# Shema.net
KiCad netlist of a schematic drawn in Altium Designer
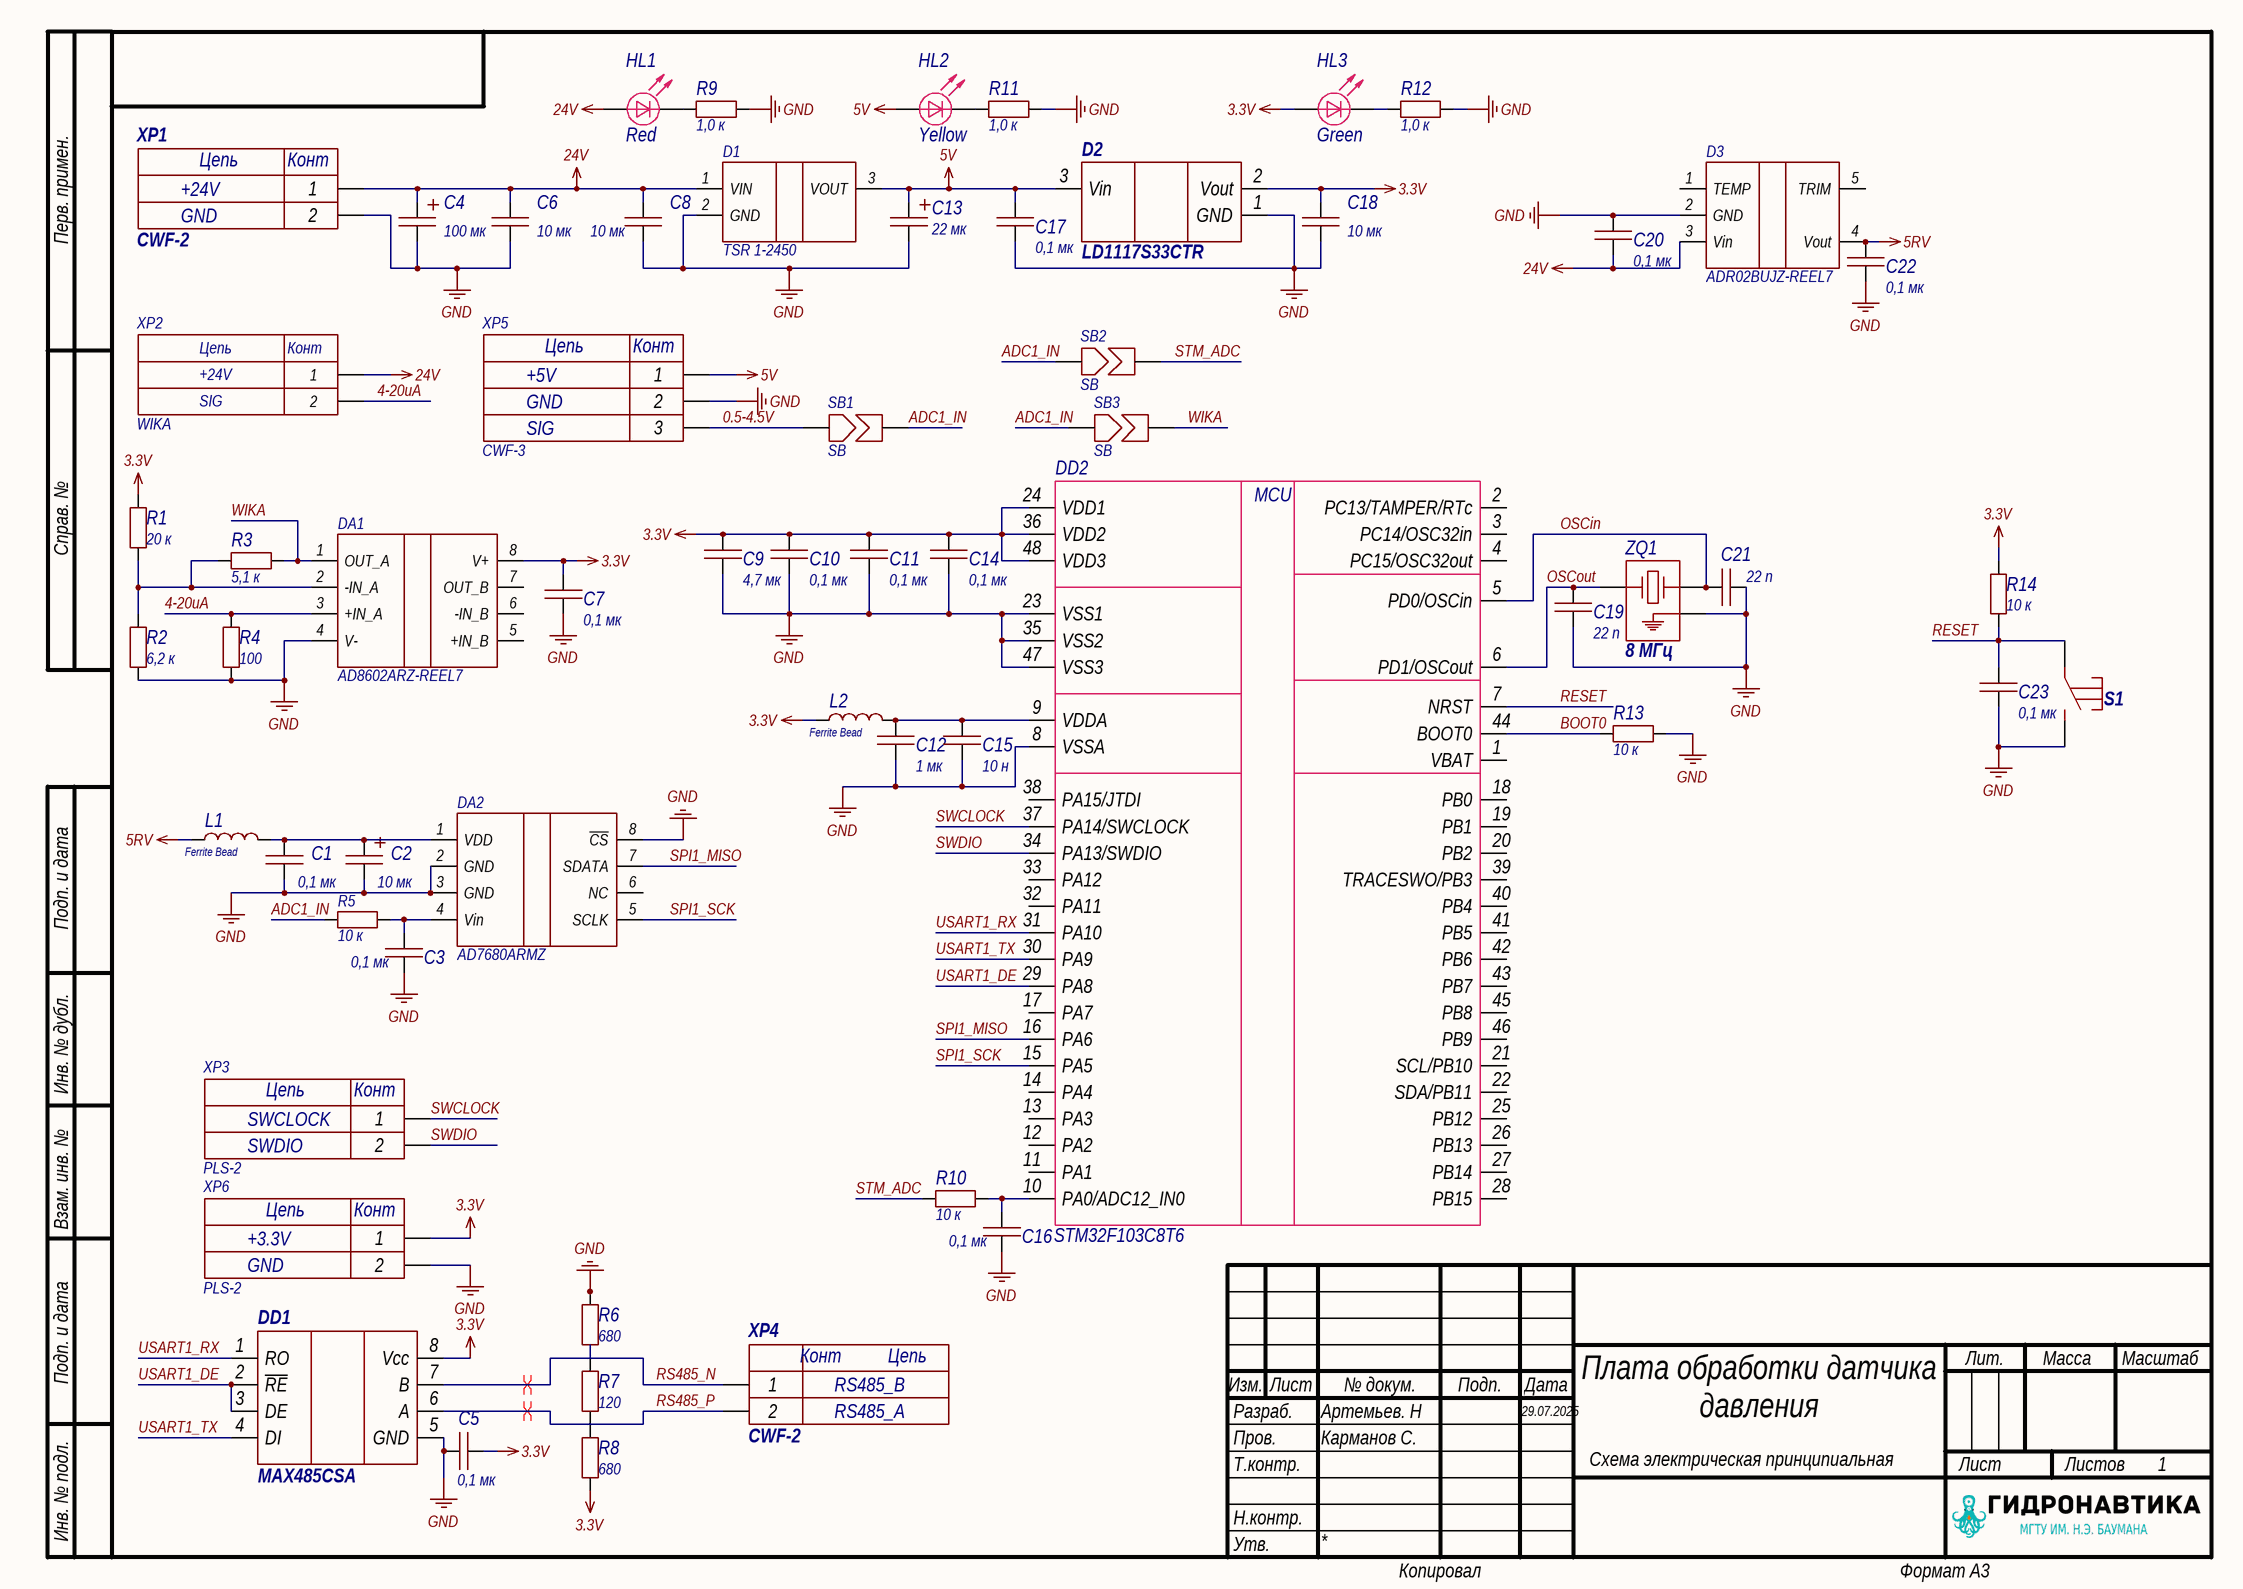
[diagram p0: Shema.SchDoc]

(export (version "E")
  (design (tool "Eeschema 10.0.6"))
  (components
    (comp (ref "C1")
      (value "0,1 мк")
      (footprint "0603C")
      (description "Конденсатор")
      (fields (field (name "PART NUMBER") "Capacitor_0,1u_10_50V_X7R_0603C") (field (name "TOLERANCE") "0,1"))
      (libsource (lib "Hydrolib") (part "Capacitor"))
    )
    (comp (ref "C2")
      (value "10 мк")
      (footprint "TC_A")
      (description "Танталовый конденсатор")
      (fields (field (name "PART NUMBER") "Capacitor_10u_10_50V_TC_A") (field (name "TOLERANCE") "0,1"))
      (libsource (lib "Hydrolib") (part "Capacitor_polar"))
    )
    (comp (ref "C3")
      (value "0,1 мк")
      (footprint "0603C")
      (description "Конденсатор")
      (fields (field (name "PART NUMBER") "Capacitor_0,1u_10_50V_X7R_0603C") (field (name "TOLERANCE") "0,1"))
      (libsource (lib "Hydrolib") (part "Capacitor"))
    )
    (comp (ref "C4")
      (value "100 мк")
      (footprint "TC_A")
      (description "Танталовый конденсатор")
      (fields (field (name "PART NUMBER") "Capacitor_100u_10_50V_TC_A") (field (name "TOLERANCE") "0,1"))
      (libsource (lib "Hydrolib") (part "Capacitor_polar"))
    )
    (comp (ref "C5")
      (value "0,1 мк")
      (footprint "0603C")
      (description "Конденсатор")
      (fields (field (name "PART NUMBER") "Capacitor_0,1u_10_50V_X7R_0603C") (field (name "TOLERANCE") "0,1"))
      (libsource (lib "Hydrolib") (part "Capacitor"))
    )
    (comp (ref "C6")
      (value "10 мк")
      (footprint "1210C")
      (description "Конденсатор")
      (fields (field (name "PART NUMBER") "Capacitor_10u_10_35V_X7R_1210C") (field (name "TOLERANCE") "0,1"))
      (libsource (lib "Hydrolib") (part "Capacitor"))
    )
    (comp (ref "C7")
      (value "0,1 мк")
      (footprint "0603C")
      (description "Конденсатор")
      (fields (field (name "PART NUMBER") "Capacitor_0,1u_10_50V_X7R_0603C") (field (name "TOLERANCE") "0,1"))
      (libsource (lib "Hydrolib") (part "Capacitor"))
    )
    (comp (ref "C8")
      (value "10 мк")
      (footprint "1210C")
      (description "Конденсатор")
      (fields (field (name "PART NUMBER") "Capacitor_10u_10_35V_X7R_1210C") (field (name "TOLERANCE") "0,1"))
      (libsource (lib "Hydrolib") (part "Capacitor"))
    )
    (comp (ref "C9")
      (value "4,7 мк")
      (footprint "1206C")
      (description "Конденсатор")
      (fields (field (name "PART NUMBER") "Capacitor_4,7u_10_50V_X7R_1206C") (field (name "TOLERANCE") "0,1"))
      (libsource (lib "Hydrolib") (part "Capacitor"))
    )
    (comp (ref "C10")
      (value "0,1 мк")
      (footprint "0603C")
      (description "Конденсатор")
      (fields (field (name "PART NUMBER") "Capacitor_0,1u_10_50V_X7R_0603C") (field (name "TOLERANCE") "0,1"))
      (libsource (lib "Hydrolib") (part "Capacitor"))
    )
    (comp (ref "C11")
      (value "0,1 мк")
      (footprint "0603C")
      (description "Конденсатор")
      (fields (field (name "PART NUMBER") "Capacitor_0,1u_10_50V_X7R_0603C") (field (name "TOLERANCE") "0,1"))
      (libsource (lib "Hydrolib") (part "Capacitor"))
    )
    (comp (ref "C12")
      (value "1 мк")
      (footprint "0603C")
      (description "Конденсатор")
      (fields (field (name "PART NUMBER") "Capacitor_1u_10_50V_X7R_0603C") (field (name "TOLERANCE") "0,1"))
      (libsource (lib "Hydrolib") (part "Capacitor"))
    )
    (comp (ref "C13")
      (value "22 мк")
      (footprint "TC_A")
      (description "Танталовый конденсатор")
      (fields (field (name "PART NUMBER") "Capacitor_22u_10_50V_TC_A") (field (name "TOLERANCE") "0,1"))
      (libsource (lib "Hydrolib") (part "Capacitor_polar"))
    )
    (comp (ref "C14")
      (value "0,1 мк")
      (footprint "0603C")
      (description "Конденсатор")
      (fields (field (name "PART NUMBER") "Capacitor_0,1u_10_50V_X7R_0603C") (field (name "TOLERANCE") "0,1"))
      (libsource (lib "Hydrolib") (part "Capacitor"))
    )
    (comp (ref "C15")
      (value "10 н")
      (footprint "0603C")
      (description "Конденсатор")
      (fields (field (name "PART NUMBER") "Capacitor_10n_10_50V_X7R_0603C") (field (name "TOLERANCE") "0,1"))
      (libsource (lib "Hydrolib") (part "Capacitor"))
    )
    (comp (ref "C16")
      (value "0,1 мк")
      (footprint "0603C")
      (description "Конденсатор")
      (fields (field (name "PART NUMBER") "Capacitor_0,1u_10_50V_X7R_0603C") (field (name "TOLERANCE") "0,1"))
      (libsource (lib "Hydrolib") (part "Capacitor"))
    )
    (comp (ref "C17")
      (value "0,1 мк")
      (footprint "0603C")
      (description "Конденсатор")
      (fields (field (name "PART NUMBER") "Capacitor_0,1u_10_50V_X7R_0603C") (field (name "TOLERANCE") "0,1"))
      (libsource (lib "Hydrolib") (part "Capacitor"))
    )
    (comp (ref "C18")
      (value "10 мк")
      (footprint "1210C")
      (description "Конденсатор")
      (fields (field (name "PART NUMBER") "Capacitor_10u_10_35V_X7R_1210C") (field (name "TOLERANCE") "0,1"))
      (libsource (lib "Hydrolib") (part "Capacitor"))
    )
    (comp (ref "C19")
      (value "22 п")
      (footprint "0603C")
      (description "Конденсатор")
      (fields (field (name "PART NUMBER") "Capacitor_22p_5_50V_X7R_0603C") (field (name "TOLERANCE") "0,05"))
      (libsource (lib "Hydrolib") (part "Capacitor"))
    )
    (comp (ref "C20")
      (value "0,1 мк")
      (footprint "0603C")
      (description "Конденсатор")
      (fields (field (name "PART NUMBER") "Capacitor_0,1u_10_50V_X7R_0603C") (field (name "TOLERANCE") "0,1"))
      (libsource (lib "Hydrolib") (part "Capacitor"))
    )
    (comp (ref "C21")
      (value "22 п")
      (footprint "0603C")
      (description "Конденсатор")
      (fields (field (name "PART NUMBER") "Capacitor_22p_5_50V_X7R_0603C") (field (name "TOLERANCE") "0,05"))
      (libsource (lib "Hydrolib") (part "Capacitor"))
    )
    (comp (ref "C22")
      (value "0,1 мк")
      (footprint "0603C")
      (description "Конденсатор")
      (fields (field (name "PART NUMBER") "Capacitor_0,1u_10_50V_X7R_0603C") (field (name "TOLERANCE") "0,1"))
      (libsource (lib "Hydrolib") (part "Capacitor"))
    )
    (comp (ref "C23")
      (value "0,1 мк")
      (footprint "0603C")
      (description "Конденсатор")
      (fields (field (name "PART NUMBER") "Capacitor_0,1u_10_50V_X7R_0603C") (field (name "TOLERANCE") "0,1"))
      (libsource (lib "Hydrolib") (part "Capacitor"))
    )
    (comp (ref "D1")
      (value "TSR 1-2450")
      (footprint "SIP3")
      (description "DC/DC преобразователь, 5Вт, вход 6.5-36В, выход 5В/ 1А")
      (libsource (lib "Hydrolib") (part "TSR 1-2450"))
    )
    (comp (ref "D2")
      (value "LD1117S33CTR")
      (footprint "SOT223")
      (description "Линейный стабилизатор напряжения")
      (libsource (lib "Hydrolib") (part "LD1117S33CTR"))
    )
    (comp (ref "D3")
      (value "ADR02BUJZ-REEL7")
      (footprint "SOT23-5")
      (description "Источник опорного напряжения, 5 В")
      (libsource (lib "Hydrolib") (part "ADR02BUJZ-REEL7"))
    )
    (comp (ref "DA1")
      (value "AD8602ARZ-REEL7")
      (footprint "SOIC-8")
      (description "2-х канальный прецизионный, широкополосный операционный усилитель с однополярным питанием")
      (libsource (lib "Hydrolib") (part "AD8602"))
    )
    (comp (ref "DA2")
      (value "AD7680ARMZ")
      (footprint "MSOP-8")
      (description "16-бит АЦП, SAR, 100Квыборок/с")
      (libsource (lib "Hydrolib") (part "AD7680ARMZ"))
    )
    (comp (ref "DD1")
      (value "MAX485CSA")
      (footprint "SOIC-8")
      (description "RS-485 приёмопередатчик")
      (libsource (lib "Hydrolib") (part "MAX485CSA"))
    )
    (comp (ref "DD2")
      (value "STM32F103C8T6")
      (footprint "LQFP48")
      (description "Микроконтроллер")
      (fields (field (name "MANUFACTURER") "ST Microelectronics") (field (name "VALUE1") "MCU"))
      (libsource (lib "Hydrolib") (part "STM32F103C8T6"))
    )
    (comp (ref "HL1")
      (value "LED")
      (footprint "0805D")
      (description "Светодиод")
      (fields (field (name "COLOR") "Red"))
      (libsource (lib "Hydrolib") (part "LED"))
    )
    (comp (ref "HL2")
      (value "LED")
      (footprint "0805D")
      (description "Светодиод")
      (fields (field (name "COLOR") "Yellow"))
      (libsource (lib "Hydrolib") (part "LED"))
    )
    (comp (ref "HL3")
      (value "LED")
      (footprint "0805D")
      (description "Светодиод")
      (fields (field (name "COLOR") "Green"))
      (libsource (lib "Hydrolib") (part "LED"))
    )
    (comp (ref "L1")
      (value "Ferrite Bead")
      (footprint "0603L")
      (fields (field (name "PART NUMBER") "Inductance"))
      (libsource (lib "Hydrolib") (part "Inductance"))
    )
    (comp (ref "L2")
      (value "Ferrite Bead")
      (footprint "0603L")
      (fields (field (name "PART NUMBER") "Inductance"))
      (libsource (lib "Hydrolib") (part "Inductance"))
    )
    (comp (ref "R1")
      (value "20 к")
      (footprint "0603R")
      (description "Резистор номиналом 20 кОм и точностью 1%")
      (fields (field (name "PART NUMBER") "Resistor_20k_1_0603") (field (name "TOLERANCE") "1%"))
      (libsource (lib "") (part "Resistor_1"))
    )
    (comp (ref "R2")
      (value "6,2 к")
      (footprint "0603R")
      (description "Резистор номиналом 6,2 кОм и точностью 1%")
      (fields (field (name "PART NUMBER") "Resistor_6.2k_1_0603") (field (name "TOLERANCE") "1%"))
      (libsource (lib "") (part "Resistor_1"))
    )
    (comp (ref "R3")
      (value "5,1 к")
      (footprint "0603R")
      (description "Резистор номиналом 5,1 кОм и точностью 1%")
      (fields (field (name "PART NUMBER") "Resistor_5.1k_1_0603") (field (name "TOLERANCE") "1%"))
      (libsource (lib "Hydrolib") (part "Resistor"))
    )
    (comp (ref "R4")
      (value "100")
      (footprint "0603R")
      (description "Резистор номиналом 100 Ом и точностью 1%")
      (fields (field (name "PART NUMBER") "Resistor_100_1_0603") (field (name "TOLERANCE") "1%"))
      (libsource (lib "") (part "Resistor_2"))
    )
    (comp (ref "R5")
      (value "10 к")
      (footprint "0603R")
      (description "Резистор номиналом 10 кОм и точностью 1%")
      (fields (field (name "PART NUMBER") "Resistor_10k_1_0603") (field (name "TOLERANCE") "1%"))
      (libsource (lib "Hydrolib") (part "Resistor"))
    )
    (comp (ref "R6")
      (value "680")
      (footprint "0603R")
      (description "Резистор номиналом 680 Ом и точностью 1%")
      (fields (field (name "PART NUMBER") "Resistor_680_1_0603") (field (name "TOLERANCE") "1%"))
      (libsource (lib "") (part "Resistor_1"))
    )
    (comp (ref "R7")
      (value "120")
      (footprint "1206R")
      (description "Резистор номиналом 120 Ом и точностью 1%")
      (fields (field (name "PART NUMBER") "Resistor_120_1_0603") (field (name "TOLERANCE") "1%"))
      (libsource (lib "") (part "Resistor_1"))
    )
    (comp (ref "R8")
      (value "680")
      (footprint "0603R")
      (description "Резистор номиналом 680 Ом и точностью 1%")
      (fields (field (name "PART NUMBER") "Resistor_680_1_0603") (field (name "TOLERANCE") "1%"))
      (libsource (lib "") (part "Resistor_1"))
    )
    (comp (ref "R9")
      (value "1,0 к")
      (footprint "0603R")
      (description "Резистор номиналом 1,0 кОм и точностью 1%")
      (fields (field (name "PART NUMBER") "Resistor_1.0k_1_0603") (field (name "TOLERANCE") "1%"))
      (libsource (lib "Hydrolib") (part "Resistor"))
    )
    (comp (ref "R10")
      (value "10 к")
      (footprint "0603R")
      (description "Резистор номиналом 10 кОм и точностью 1%")
      (fields (field (name "PART NUMBER") "Resistor_10k_1_0603") (field (name "TOLERANCE") "1%"))
      (libsource (lib "Hydrolib") (part "Resistor"))
    )
    (comp (ref "R11")
      (value "1,0 к")
      (footprint "0603R")
      (description "Резистор номиналом 1,0 кОм и точностью 1%")
      (fields (field (name "PART NUMBER") "Resistor_1.0k_1_0603") (field (name "TOLERANCE") "1%"))
      (libsource (lib "Hydrolib") (part "Resistor"))
    )
    (comp (ref "R12")
      (value "1,0 к")
      (footprint "0603R")
      (description "Резистор номиналом 1,0 кОм и точностью 1%")
      (fields (field (name "PART NUMBER") "Resistor_1.0k_1_0603") (field (name "TOLERANCE") "1%"))
      (libsource (lib "Hydrolib") (part "Resistor"))
    )
    (comp (ref "R13")
      (value "10 к")
      (footprint "0603R")
      (description "Резистор номиналом 10 кОм и точностью 1%")
      (fields (field (name "PART NUMBER") "Resistor_10k_1_0603") (field (name "TOLERANCE") "1%"))
      (libsource (lib "Hydrolib") (part "Resistor"))
    )
    (comp (ref "R14")
      (value "10 к")
      (footprint "0603R")
      (description "Резистор номиналом 10 кОм и точностью 1%")
      (fields (field (name "PART NUMBER") "Resistor_10k_1_0603") (field (name "TOLERANCE") "1%"))
      (libsource (lib "") (part "Resistor_2"))
    )
    (comp (ref "S1")
      (value "Tact_button")
      (footprint "Button_SMD_10mm")
      (description "Тактовая кнопка")
      (libsource (lib "Hydrolib") (part "Tact_button"))
    )
    (comp (ref "SB1")
      (value "SB")
      (footprint "0805SB")
      (description "Solder bridge, мост припоя, запаиваемая перемычка, net tie, jumper")
      (libsource (lib "Hydrolib") (part "SB"))
    )
    (comp (ref "SB2")
      (value "SB")
      (footprint "0805SB")
      (description "Solder bridge, мост припоя, запаиваемая перемычка, net tie, jumper")
      (libsource (lib "Hydrolib") (part "SB"))
    )
    (comp (ref "SB3")
      (value "SB")
      (footprint "0805SB")
      (description "Solder bridge, мост припоя, запаиваемая перемычка, net tie, jumper")
      (libsource (lib "Hydrolib") (part "SB"))
    )
    (comp (ref "XP1")
      (value "CWF-2")
      (footprint "CWF-2")
      (description "2-пиновый разъем с ключом")
      (fields (field (name "VALUE2") "GND") (field (name "VALUE1") "+24V"))
      (libsource (lib "Hydrolib") (part "Conn_2pin"))
    )
    (comp (ref "XP2") (value "WIKA") (footprint "WIKA_PCB") (libsource (lib "Hydrolib") (part "WIKA")))
    (comp (ref "XP3")
      (value "PLS-2")
      (footprint "PLS2")
      (description "Гребенка 2 пина")
      (fields (field (name "VALUE2") "SWDIO") (field (name "VALUE1") "SWCLOCK"))
      (libsource (lib "Hydrolib") (part "Conn_2pin"))
    )
    (comp (ref "XP4")
      (value "CWF-2")
      (footprint "CWF-2")
      (description "2-пиновый разъем с ключом")
      (fields (field (name "VALUE2") "RS485_A") (field (name "VALUE1") "RS485_B"))
      (libsource (lib "Hydrolib") (part "Conn_2pin"))
    )
    (comp (ref "XP5")
      (value "CWF-3")
      (footprint "CWF-3")
      (description "3-пиновый разъем с ключом")
      (fields (field (name "VALUE3") "SIG") (field (name "VALUE2") "GND") (field (name "VALUE1") "+5V"))
      (libsource (lib "Hydrolib") (part "Conn_3pin"))
    )
    (comp (ref "XP6")
      (value "PLS-2")
      (footprint "PLS2")
      (description "Гребенка 2 пина")
      (fields (field (name "VALUE2") "GND") (field (name "VALUE1") "+3.3V"))
      (libsource (lib "Hydrolib") (part "Conn_2pin"))
    )
    (comp (ref "ZQ1")
      (value "8 МГц")
      (footprint "QSMD3.2x2.5")
      (description "Кварцевый резонатор с входом земли")
      (fields (field (name "PART NUMBER") "XTAL_GND"))
      (libsource (lib "Hydrolib") (part "XTAL_GND"))
    )
  )
  (nets
    (net (code "1") (name "/0.5-4.5V") (class "Default")
      (node (ref "SB1") (pin "1") (pinfunction "1_1") (pintype "passive"))
      (node (ref "XP5") (pin "3") (pinfunction "3_3") (pintype "passive"))
    )
    (net (code "2") (name "/4-20uA") (class "Default")
      (node (ref "DA1") (pin "3") (pinfunction "+IN_A_3") (pintype "passive"))
      (node (ref "R4") (pin "1") (pinfunction "1_1") (pintype "passive"))
      (node (ref "XP2") (pin "2") (pinfunction "2_2") (pintype "passive"))
    )
    (net (code "3") (name "/ADC1_IN") (class "Default")
      (node (ref "R5") (pin "1") (pinfunction "1_1") (pintype "passive"))
      (node (ref "SB1") (pin "2") (pinfunction "2_2") (pintype "passive"))
      (node (ref "SB2") (pin "1") (pinfunction "1_1") (pintype "passive"))
      (node (ref "SB3") (pin "1") (pinfunction "1_1") (pintype "passive"))
    )
    (net (code "4") (name "/BOOT0") (class "Default")
      (node (ref "DD2") (pin "44") (pinfunction "BOOT0_44") (pintype "passive"))
      (node (ref "R13") (pin "1") (pinfunction "1_1") (pintype "passive"))
    )
    (net (code "5") (name "/OSCin") (class "Default")
      (node (ref "C21") (pin "2") (pinfunction "2_2") (pintype "passive"))
      (node (ref "DD2") (pin "5") (pinfunction "PD0/OSCin_5") (pintype "passive"))
      (node (ref "ZQ1") (pin "2") (pinfunction "2_2") (pintype "passive"))
    )
    (net (code "6") (name "/OSCout") (class "Default")
      (node (ref "C19") (pin "1") (pinfunction "1_1") (pintype "passive"))
      (node (ref "DD2") (pin "6") (pinfunction "PD1/OSCout_6") (pintype "passive"))
      (node (ref "ZQ1") (pin "1") (pinfunction "1_1") (pintype "passive"))
    )
    (net (code "7") (name "/RESET") (class "Default")
      (node (ref "C23") (pin "1") (pinfunction "1_1") (pintype "passive"))
      (node (ref "DD2") (pin "7") (pinfunction "NRST_7") (pintype "passive"))
      (node (ref "R14") (pin "2") (pinfunction "2_2") (pintype "passive"))
      (node (ref "S1") (pin "1") (pinfunction "1_1") (pintype "passive"))
    )
    (net (code "8") (name "/RS485_N") (class "Default")
      (node (ref "DD1") (pin "7") (pinfunction "B_7") (pintype "passive"))
      (node (ref "R6") (pin "1") (pinfunction "1_1") (pintype "passive"))
      (node (ref "R7") (pin "2") (pinfunction "2_2") (pintype "passive"))
      (node (ref "XP4") (pin "1") (pinfunction "1_1") (pintype "passive"))
    )
    (net (code "9") (name "/RS485_P") (class "Default")
      (node (ref "DD1") (pin "6") (pinfunction "A_6") (pintype "passive"))
      (node (ref "R7") (pin "1") (pinfunction "1_1") (pintype "passive"))
      (node (ref "R8") (pin "2") (pinfunction "2_2") (pintype "passive"))
      (node (ref "XP4") (pin "2") (pinfunction "2_2") (pintype "passive"))
    )
    (net (code "10") (name "/SPI1_MISO") (class "Default")
      (node (ref "DA2") (pin "7") (pinfunction "SDATA_7") (pintype "passive"))
      (node (ref "DD2") (pin "16") (pinfunction "PA6_16") (pintype "passive"))
    )
    (net (code "11") (name "/SPI1_SCK") (class "Default")
      (node (ref "DA2") (pin "5") (pinfunction "SCLK_5") (pintype "passive"))
      (node (ref "DD2") (pin "15") (pinfunction "PA5_15") (pintype "passive"))
    )
    (net (code "12") (name "/STM_ADC") (class "Default")
      (node (ref "R10") (pin "1") (pinfunction "1_1") (pintype "passive"))
      (node (ref "SB2") (pin "2") (pinfunction "2_2") (pintype "passive"))
    )
    (net (code "13") (name "/SWCLOCK") (class "Default")
      (node (ref "DD2") (pin "37") (pinfunction "PA14/SWCLOCK_37") (pintype "passive"))
      (node (ref "XP3") (pin "1") (pinfunction "1_1") (pintype "passive"))
    )
    (net (code "14") (name "/SWDIO") (class "Default")
      (node (ref "DD2") (pin "34") (pinfunction "PA13/SWDIO_34") (pintype "passive"))
      (node (ref "XP3") (pin "2") (pinfunction "2_2") (pintype "passive"))
    )
    (net (code "15") (name "/USART1_DE") (class "Default")
      (node (ref "DD1") (pin "2") (pinfunction "RE_2") (pintype "passive"))
      (node (ref "DD1") (pin "3") (pinfunction "DE_3") (pintype "passive"))
      (node (ref "DD2") (pin "29") (pinfunction "PA8_29") (pintype "passive"))
    )
    (net (code "16") (name "/USART1_RX") (class "Default")
      (node (ref "DD1") (pin "1") (pinfunction "RO_1") (pintype "passive"))
      (node (ref "DD2") (pin "31") (pinfunction "PA10_31") (pintype "passive"))
    )
    (net (code "17") (name "/USART1_TX") (class "Default")
      (node (ref "DD1") (pin "4") (pinfunction "DI_4") (pintype "passive"))
      (node (ref "DD2") (pin "30") (pinfunction "PA9_30") (pintype "passive"))
    )
    (net (code "18") (name "/WIKA") (class "Default")
      (node (ref "DA1") (pin "1") (pinfunction "OUT_A_1") (pintype "passive"))
      (node (ref "R3") (pin "2") (pinfunction "2_2") (pintype "passive"))
      (node (ref "SB3") (pin "2") (pinfunction "2_2") (pintype "passive"))
    )
    (net (code "19") (name "3.3V") (class "Default")
      (node (ref "C10") (pin "2") (pinfunction "2_2") (pintype "passive"))
      (node (ref "C11") (pin "2") (pinfunction "2_2") (pintype "passive"))
      (node (ref "C14") (pin "2") (pinfunction "2_2") (pintype "passive"))
      (node (ref "C18") (pin "2") (pinfunction "2_2") (pintype "passive"))
      (node (ref "C5") (pin "2") (pinfunction "2_2") (pintype "passive"))
      (node (ref "C7") (pin "2") (pinfunction "2_2") (pintype "passive"))
      (node (ref "C9") (pin "2") (pinfunction "2_2") (pintype "passive"))
      (node (ref "D2") (pin "2") (pinfunction "Vout_2") (pintype "passive"))
      (node (ref "DA1") (pin "8") (pinfunction "V+_8") (pintype "passive"))
      (node (ref "DD1") (pin "8") (pinfunction "Vcc_8") (pintype "passive"))
      (node (ref "DD2") (pin "24") (pinfunction "VDD1_24") (pintype "passive"))
      (node (ref "DD2") (pin "36") (pinfunction "VDD2_36") (pintype "passive"))
      (node (ref "DD2") (pin "48") (pinfunction "VDD3_48") (pintype "passive"))
      (node (ref "HL3") (pin "1") (pinfunction "1_1") (pintype "passive"))
      (node (ref "L2") (pin "1") (pinfunction "1_1") (pintype "passive"))
      (node (ref "R1") (pin "2") (pinfunction "2_2") (pintype "passive"))
      (node (ref "R14") (pin "1") (pinfunction "1_1") (pintype "passive"))
      (node (ref "R8") (pin "1") (pinfunction "1_1") (pintype "passive"))
      (node (ref "XP6") (pin "1") (pinfunction "1_1") (pintype "passive"))
    )
    (net (code "20") (name "5RV") (class "Default")
      (node (ref "C22") (pin "2") (pinfunction "2_2") (pintype "passive"))
      (node (ref "D3") (pin "4") (pinfunction "Vout_4") (pintype "passive"))
      (node (ref "L1") (pin "1") (pinfunction "1_1") (pintype "passive"))
    )
    (net (code "21") (name "5V") (class "Default")
      (node (ref "C13") (pin "1") (pinfunction "1_1") (pintype "passive"))
      (node (ref "C17") (pin "2") (pinfunction "2_2") (pintype "passive"))
      (node (ref "D1") (pin "3") (pinfunction "VOUT_3") (pintype "passive"))
      (node (ref "D2") (pin "3") (pinfunction "Vin_3") (pintype "passive"))
      (node (ref "HL2") (pin "1") (pinfunction "1_1") (pintype "passive"))
      (node (ref "XP5") (pin "1") (pinfunction "1_1") (pintype "passive"))
    )
    (net (code "22") (name "24V") (class "Default")
      (node (ref "C20") (pin "1") (pinfunction "1_1") (pintype "passive"))
      (node (ref "C4") (pin "1") (pinfunction "1_1") (pintype "passive"))
      (node (ref "C6") (pin "2") (pinfunction "2_2") (pintype "passive"))
      (node (ref "C8") (pin "2") (pinfunction "2_2") (pintype "passive"))
      (node (ref "D1") (pin "1") (pinfunction "VIN_1") (pintype "passive"))
      (node (ref "D3") (pin "3") (pinfunction "Vin_3") (pintype "passive"))
      (node (ref "HL1") (pin "1") (pinfunction "1_1") (pintype "passive"))
      (node (ref "XP1") (pin "1") (pinfunction "1_1") (pintype "passive"))
      (node (ref "XP2") (pin "1") (pinfunction "1_1") (pintype "passive"))
    )
    (net (code "23") (name "GND") (class "Default")
      (node (ref "C1") (pin "1") (pinfunction "1_1") (pintype "passive"))
      (node (ref "C10") (pin "1") (pinfunction "1_1") (pintype "passive"))
      (node (ref "C11") (pin "1") (pinfunction "1_1") (pintype "passive"))
      (node (ref "C12") (pin "1") (pinfunction "1_1") (pintype "passive"))
      (node (ref "C13") (pin "2") (pinfunction "2_2") (pintype "passive"))
      (node (ref "C14") (pin "1") (pinfunction "1_1") (pintype "passive"))
      (node (ref "C15") (pin "1") (pinfunction "1_1") (pintype "passive"))
      (node (ref "C16") (pin "1") (pinfunction "1_1") (pintype "passive"))
      (node (ref "C17") (pin "1") (pinfunction "1_1") (pintype "passive"))
      (node (ref "C18") (pin "1") (pinfunction "1_1") (pintype "passive"))
      (node (ref "C19") (pin "2") (pinfunction "2_2") (pintype "passive"))
      (node (ref "C2") (pin "2") (pinfunction "2_2") (pintype "passive"))
      (node (ref "C20") (pin "2") (pinfunction "2_2") (pintype "passive"))
      (node (ref "C21") (pin "1") (pinfunction "1_1") (pintype "passive"))
      (node (ref "C22") (pin "1") (pinfunction "1_1") (pintype "passive"))
      (node (ref "C23") (pin "2") (pinfunction "2_2") (pintype "passive"))
      (node (ref "C3") (pin "1") (pinfunction "1_1") (pintype "passive"))
      (node (ref "C4") (pin "2") (pinfunction "2_2") (pintype "passive"))
      (node (ref "C5") (pin "1") (pinfunction "1_1") (pintype "passive"))
      (node (ref "C6") (pin "1") (pinfunction "1_1") (pintype "passive"))
      (node (ref "C7") (pin "1") (pinfunction "1_1") (pintype "passive"))
      (node (ref "C8") (pin "1") (pinfunction "1_1") (pintype "passive"))
      (node (ref "C9") (pin "1") (pinfunction "1_1") (pintype "passive"))
      (node (ref "D1") (pin "2") (pinfunction "GND_2") (pintype "passive"))
      (node (ref "D2") (pin "1") (pinfunction "GND_1") (pintype "passive"))
      (node (ref "D3") (pin "2") (pinfunction "GND_2") (pintype "passive"))
      (node (ref "DA1") (pin "4") (pinfunction "V-_4") (pintype "passive"))
      (node (ref "DA2") (pin "2") (pinfunction "GND_2") (pintype "passive"))
      (node (ref "DA2") (pin "3") (pinfunction "GND_3") (pintype "passive"))
      (node (ref "DA2") (pin "8") (pinfunction "~{CS}_8") (pintype "passive"))
      (node (ref "DD1") (pin "5") (pinfunction "GND_5") (pintype "passive"))
      (node (ref "DD2") (pin "23") (pinfunction "VSS1_23") (pintype "passive"))
      (node (ref "DD2") (pin "35") (pinfunction "VSS2_35") (pintype "passive"))
      (node (ref "DD2") (pin "47") (pinfunction "VSS3_47") (pintype "passive"))
      (node (ref "DD2") (pin "8") (pinfunction "VSSA_8") (pintype "passive"))
      (node (ref "R11") (pin "2") (pinfunction "2_2") (pintype "passive"))
      (node (ref "R12") (pin "2") (pinfunction "2_2") (pintype "passive"))
      (node (ref "R13") (pin "2") (pinfunction "2_2") (pintype "passive"))
      (node (ref "R2") (pin "1") (pinfunction "1_1") (pintype "passive"))
      (node (ref "R4") (pin "2") (pinfunction "2_2") (pintype "passive"))
      (node (ref "R6") (pin "2") (pinfunction "2_2") (pintype "passive"))
      (node (ref "R9") (pin "2") (pinfunction "2_2") (pintype "passive"))
      (node (ref "S1") (pin "2") (pinfunction "2_2") (pintype "passive"))
      (node (ref "XP1") (pin "2") (pinfunction "2_2") (pintype "passive"))
      (node (ref "XP5") (pin "2") (pinfunction "2_2") (pintype "passive"))
      (node (ref "XP6") (pin "2") (pinfunction "2_2") (pintype "passive"))
      (node (ref "ZQ1") (pin "3") (pinfunction "3_3") (pintype "passive"))
    )
    (net (code "24") (name "Net-(DA1--IN_A)") (class "Default")
      (node (ref "DA1") (pin "2") (pinfunction "-IN_A_2") (pintype "passive"))
      (node (ref "R1") (pin "1") (pinfunction "1_1") (pintype "passive"))
      (node (ref "R2") (pin "2") (pinfunction "2_2") (pintype "passive"))
      (node (ref "R3") (pin "1") (pinfunction "1_1") (pintype "passive"))
    )
    (net (code "25") (name "Net-(DA2-VDD)") (class "Default")
      (node (ref "C1") (pin "2") (pinfunction "2_2") (pintype "passive"))
      (node (ref "C2") (pin "1") (pinfunction "1_1") (pintype "passive"))
      (node (ref "DA2") (pin "1") (pinfunction "VDD_1") (pintype "passive"))
      (node (ref "L1") (pin "2") (pinfunction "2_2") (pintype "passive"))
    )
    (net (code "26") (name "Net-(DA2-Vin)") (class "Default")
      (node (ref "C3") (pin "2") (pinfunction "2_2") (pintype "passive"))
      (node (ref "DA2") (pin "4") (pinfunction "Vin_4") (pintype "passive"))
      (node (ref "R5") (pin "2") (pinfunction "2_2") (pintype "passive"))
    )
    (net (code "27") (name "Net-(DD2-PA0{slash}ADC12_IN0)") (class "Default")
      (node (ref "C16") (pin "2") (pinfunction "2_2") (pintype "passive"))
      (node (ref "DD2") (pin "10") (pinfunction "PA0/ADC12_IN0_10") (pintype "passive"))
      (node (ref "R10") (pin "2") (pinfunction "2_2") (pintype "passive"))
    )
    (net (code "28") (name "Net-(DD2-VDDA)") (class "Default")
      (node (ref "C12") (pin "2") (pinfunction "2_2") (pintype "passive"))
      (node (ref "C15") (pin "2") (pinfunction "2_2") (pintype "passive"))
      (node (ref "DD2") (pin "9") (pinfunction "VDDA_9") (pintype "passive"))
      (node (ref "L2") (pin "2") (pinfunction "2_2") (pintype "passive"))
    )
    (net (code "29") (name "Net-(HL1-Pad2)") (class "Default")
      (node (ref "HL1") (pin "2") (pinfunction "2_2") (pintype "passive"))
      (node (ref "R9") (pin "1") (pinfunction "1_1") (pintype "passive"))
    )
    (net (code "30") (name "Net-(HL2-Pad2)") (class "Default")
      (node (ref "HL2") (pin "2") (pinfunction "2_2") (pintype "passive"))
      (node (ref "R11") (pin "1") (pinfunction "1_1") (pintype "passive"))
    )
    (net (code "31") (name "Net-(HL3-Pad2)") (class "Default")
      (node (ref "HL3") (pin "2") (pinfunction "2_2") (pintype "passive"))
      (node (ref "R12") (pin "1") (pinfunction "1_1") (pintype "passive"))
    )
    (net (code "32") (name "unconnected-(D3-TEMP-Pad1)") (class "Default")
      (node (ref "D3") (pin "1") (pinfunction "TEMP_1") (pintype "passive"))
    )
    (net (code "33") (name "unconnected-(D3-TRIM-Pad5)") (class "Default")
      (node (ref "D3") (pin "5") (pinfunction "TRIM_5") (pintype "passive"))
    )
    (net (code "34") (name "unconnected-(DA1-+IN_B-Pad5)") (class "Default")
      (node (ref "DA1") (pin "5") (pinfunction "+IN_B_5") (pintype "passive"))
    )
    (net (code "35") (name "unconnected-(DA1--IN_B-Pad6)") (class "Default")
      (node (ref "DA1") (pin "6") (pinfunction "-IN_B_6") (pintype "passive"))
    )
    (net (code "36") (name "unconnected-(DA1-OUT_B-Pad7)") (class "Default")
      (node (ref "DA1") (pin "7") (pinfunction "OUT_B_7") (pintype "passive"))
    )
    (net (code "37") (name "unconnected-(DA2-NC-Pad6)") (class "Default")
      (node (ref "DA2") (pin "6") (pinfunction "NC_6") (pintype "passive"))
    )
    (net (code "38") (name "unconnected-(DD2-PA1-Pad11)") (class "Default")
      (node (ref "DD2") (pin "11") (pinfunction "PA1_11") (pintype "passive"))
    )
    (net (code "39") (name "unconnected-(DD2-PA2-Pad12)") (class "Default")
      (node (ref "DD2") (pin "12") (pinfunction "PA2_12") (pintype "passive"))
    )
    (net (code "40") (name "unconnected-(DD2-PA3-Pad13)") (class "Default")
      (node (ref "DD2") (pin "13") (pinfunction "PA3_13") (pintype "passive"))
    )
    (net (code "41") (name "unconnected-(DD2-PA4-Pad14)") (class "Default")
      (node (ref "DD2") (pin "14") (pinfunction "PA4_14") (pintype "passive"))
    )
    (net (code "42") (name "unconnected-(DD2-PA7-Pad17)") (class "Default")
      (node (ref "DD2") (pin "17") (pinfunction "PA7_17") (pintype "passive"))
    )
    (net (code "43") (name "unconnected-(DD2-PA11-Pad32)") (class "Default")
      (node (ref "DD2") (pin "32") (pinfunction "PA11_32") (pintype "passive"))
    )
    (net (code "44") (name "unconnected-(DD2-PA12-Pad33)") (class "Default")
      (node (ref "DD2") (pin "33") (pinfunction "PA12_33") (pintype "passive"))
    )
    (net (code "45") (name "unconnected-(DD2-PA15{slash}JTDI-Pad38)") (class "Default")
      (node (ref "DD2") (pin "38") (pinfunction "PA15/JTDI_38") (pintype "passive"))
    )
    (net (code "46") (name "unconnected-(DD2-PB0-Pad18)") (class "Default")
      (node (ref "DD2") (pin "18") (pinfunction "PB0_18") (pintype "passive"))
    )
    (net (code "47") (name "unconnected-(DD2-PB1-Pad19)") (class "Default")
      (node (ref "DD2") (pin "19") (pinfunction "PB1_19") (pintype "passive"))
    )
    (net (code "48") (name "unconnected-(DD2-PB2-Pad20)") (class "Default")
      (node (ref "DD2") (pin "20") (pinfunction "PB2_20") (pintype "passive"))
    )
    (net (code "49") (name "unconnected-(DD2-PB4-Pad40)") (class "Default")
      (node (ref "DD2") (pin "40") (pinfunction "PB4_40") (pintype "passive"))
    )
    (net (code "50") (name "unconnected-(DD2-PB5-Pad41)") (class "Default")
      (node (ref "DD2") (pin "41") (pinfunction "PB5_41") (pintype "passive"))
    )
    (net (code "51") (name "unconnected-(DD2-PB6-Pad42)") (class "Default")
      (node (ref "DD2") (pin "42") (pinfunction "PB6_42") (pintype "passive"))
    )
    (net (code "52") (name "unconnected-(DD2-PB7-Pad43)") (class "Default")
      (node (ref "DD2") (pin "43") (pinfunction "PB7_43") (pintype "passive"))
    )
    (net (code "53") (name "unconnected-(DD2-PB8-Pad45)") (class "Default")
      (node (ref "DD2") (pin "45") (pinfunction "PB8_45") (pintype "passive"))
    )
    (net (code "54") (name "unconnected-(DD2-PB9-Pad46)") (class "Default")
      (node (ref "DD2") (pin "46") (pinfunction "PB9_46") (pintype "passive"))
    )
    (net (code "55") (name "unconnected-(DD2-PB12-Pad25)") (class "Default")
      (node (ref "DD2") (pin "25") (pinfunction "PB12_25") (pintype "passive"))
    )
    (net (code "56") (name "unconnected-(DD2-PB13-Pad26)") (class "Default")
      (node (ref "DD2") (pin "26") (pinfunction "PB13_26") (pintype "passive"))
    )
    (net (code "57") (name "unconnected-(DD2-PB14-Pad27)") (class "Default")
      (node (ref "DD2") (pin "27") (pinfunction "PB14_27") (pintype "passive"))
    )
    (net (code "58") (name "unconnected-(DD2-PB15-Pad28)") (class "Default")
      (node (ref "DD2") (pin "28") (pinfunction "PB15_28") (pintype "passive"))
    )
    (net (code "59") (name "unconnected-(DD2-PC13{slash}TAMPER{slash}RTc-Pad2)") (class "Default")
      (node (ref "DD2") (pin "2") (pinfunction "PC13/TAMPER/RTc_2") (pintype "passive"))
    )
    (net (code "60") (name "unconnected-(DD2-PC14{slash}OSC32in-Pad3)") (class "Default")
      (node (ref "DD2") (pin "3") (pinfunction "PC14/OSC32in_3") (pintype "passive"))
    )
    (net (code "61") (name "unconnected-(DD2-PC15{slash}OSC32out-Pad4)") (class "Default")
      (node (ref "DD2") (pin "4") (pinfunction "PC15/OSC32out_4") (pintype "passive"))
    )
    (net (code "62") (name "unconnected-(DD2-SCL{slash}PB10-Pad21)") (class "Default")
      (node (ref "DD2") (pin "21") (pinfunction "SCL/PB10_21") (pintype "passive"))
    )
    (net (code "63") (name "unconnected-(DD2-SDA{slash}PB11-Pad22)") (class "Default")
      (node (ref "DD2") (pin "22") (pinfunction "SDA/PB11_22") (pintype "passive"))
    )
    (net (code "64") (name "unconnected-(DD2-TRACESWO{slash}PB3-Pad39)") (class "Default")
      (node (ref "DD2") (pin "39") (pinfunction "TRACESWO/PB3_39") (pintype "passive"))
    )
    (net (code "65") (name "unconnected-(DD2-VBAT-Pad1)") (class "Default")
      (node (ref "DD2") (pin "1") (pinfunction "VBAT_1") (pintype "passive"))
    )
  )
)
